# 3-RF.net
KiCad netlist of a schematic drawn in Altium Designer
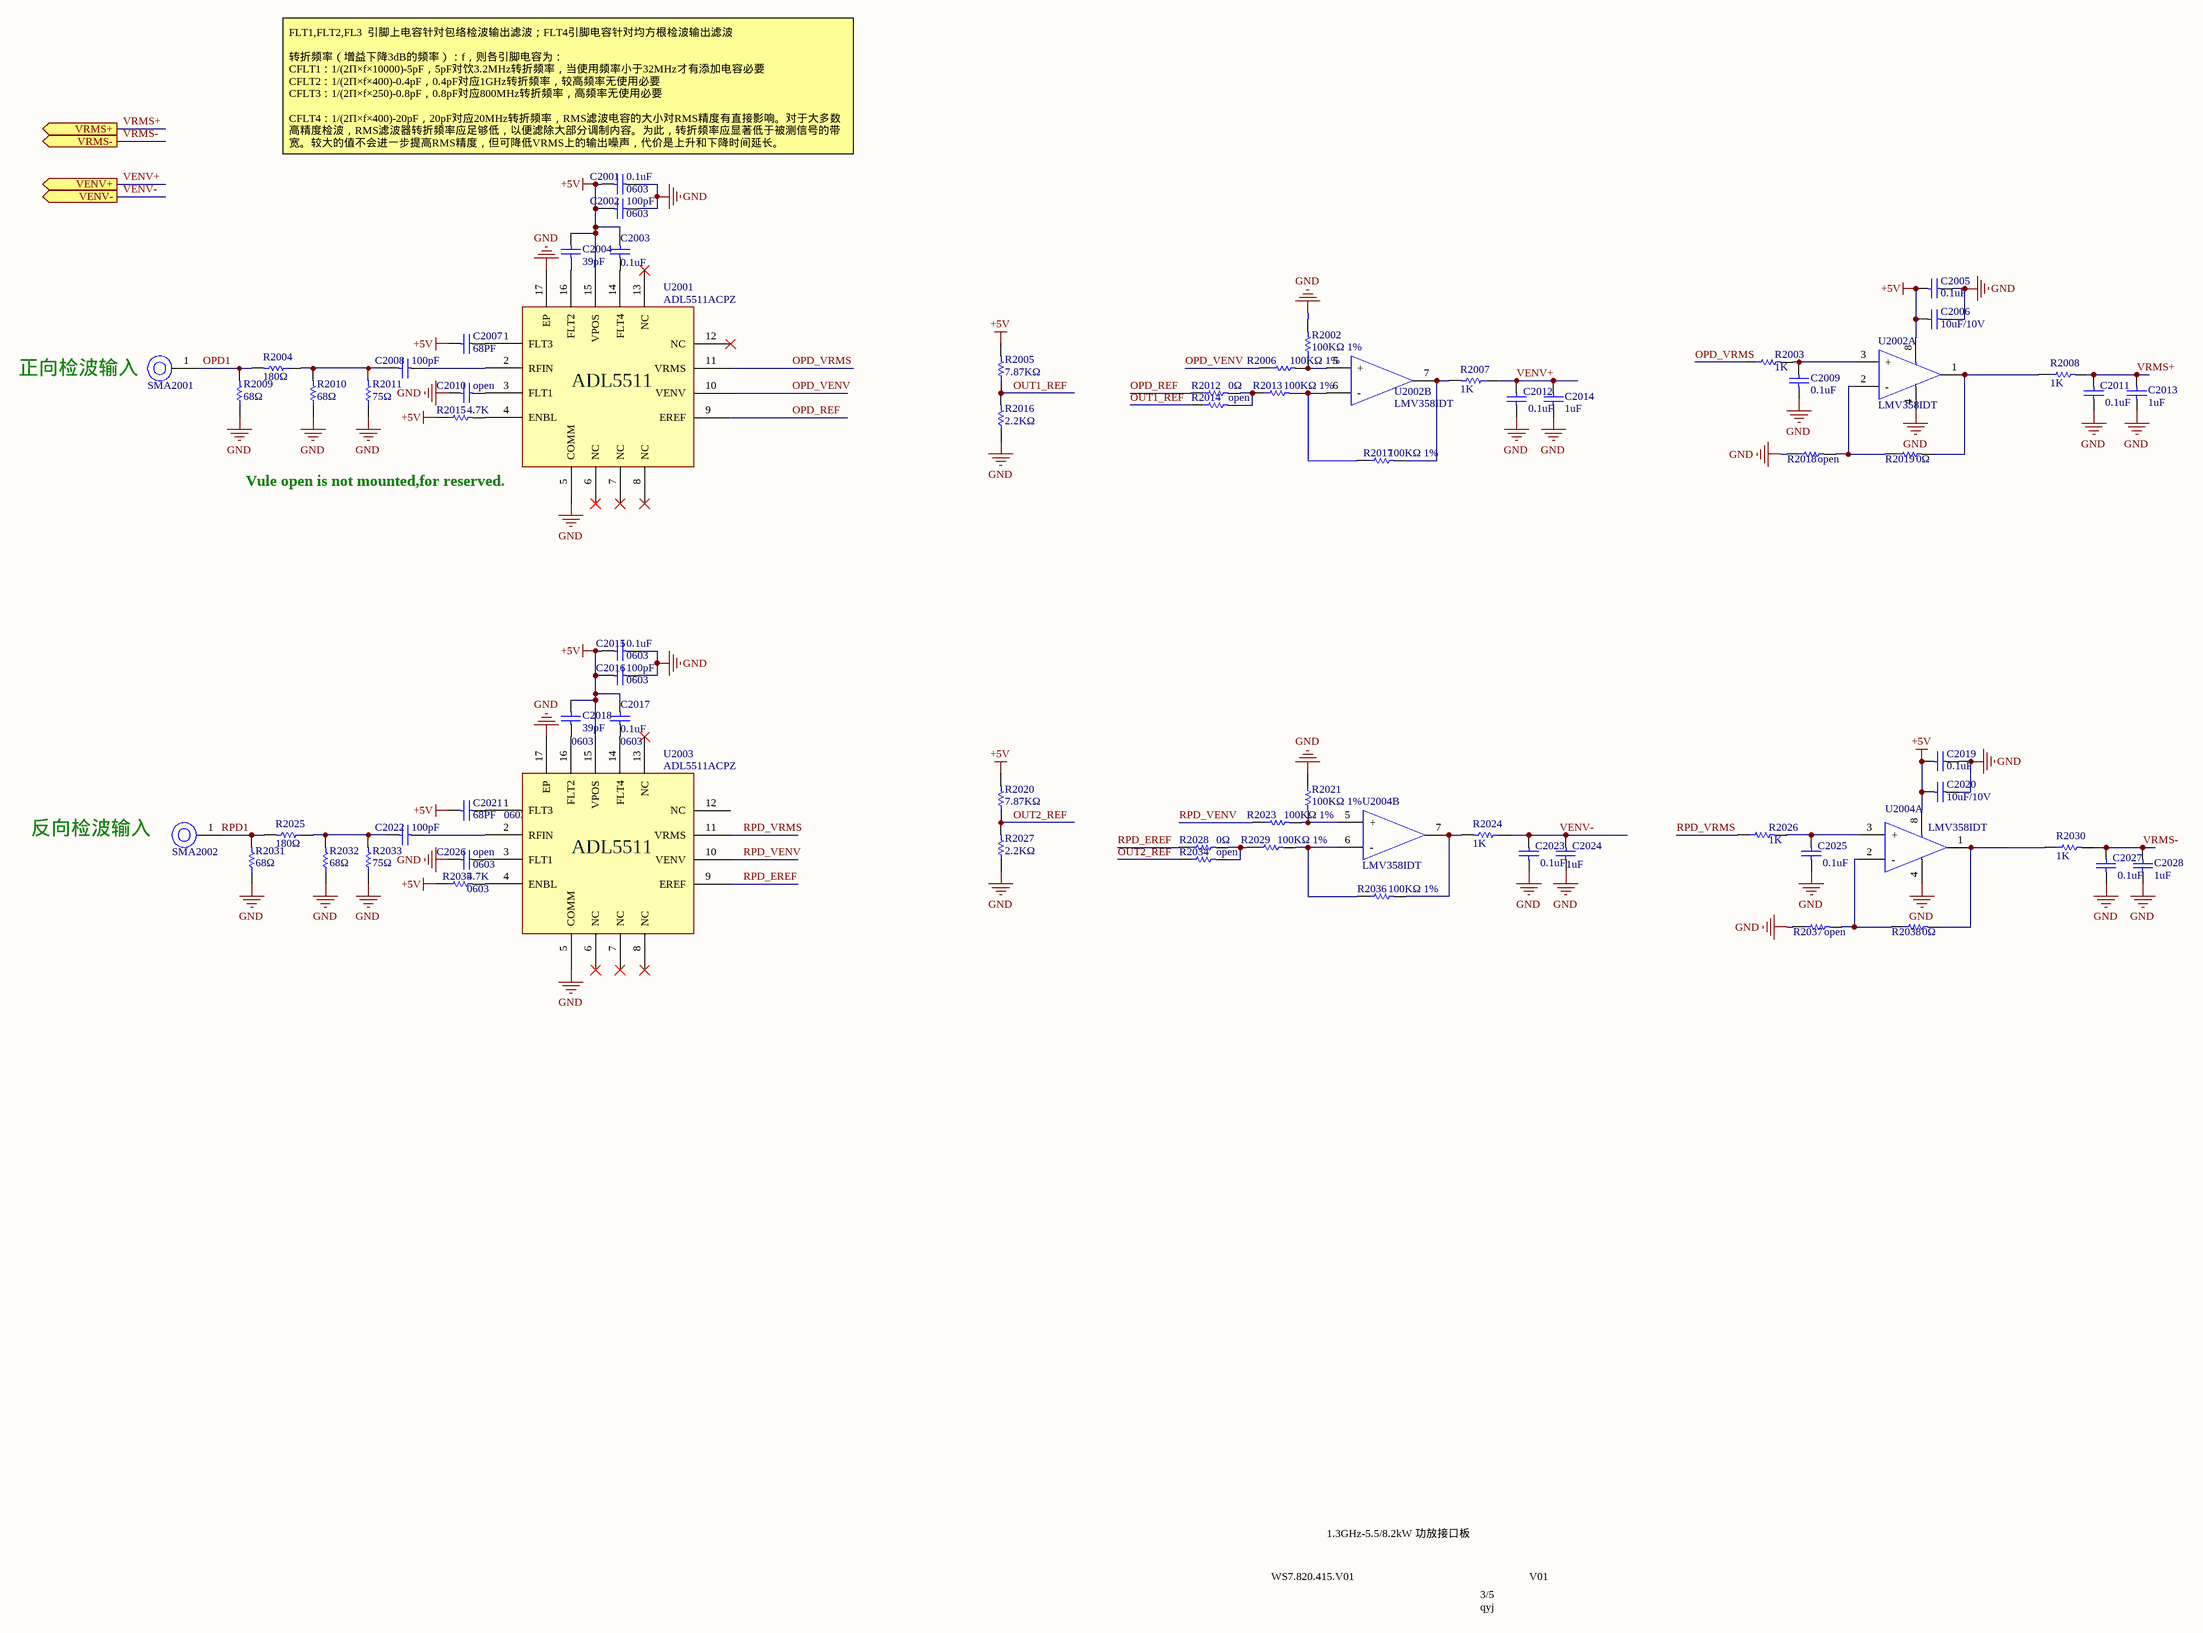
[diagram p0: 3-RF.SchDoc]

(export (version "E")
  (design (tool "Eeschema 10.0.6"))
  (components
    (comp (ref "C2001")
      (value "0.1uF")
      (footprint "C0603")
      (description "贴片电容_GRM188R71H104KA01D_0.1uF±10%,50V,0603")
      (libsource (lib "20贴片电容0603") (part "0.1uF贴片电容"))
    )
    (comp (ref "C2002")
      (value "100pF")
      (footprint "C0603")
      (description "贴片电容_100pF±10%,50V,0603")
      (libsource (lib "20贴片电容0603") (part "1000pF贴片电容"))
    )
    (comp (ref "C2003")
      (value "0.1uF")
      (footprint "C0603")
      (description "贴片电容_GRM188R71H104KA01D_0.1uF±10%,50V,0603")
      (libsource (lib "20贴片电容0603") (part "0.1uF贴片电容"))
    )
    (comp (ref "C2004")
      (value "39pF")
      (footprint "C0603")
      (description "GRM1885C1H390JA01D_39pF±5%,50V,0603")
      (libsource (lib "20贴片电容0603") (part "10pF贴片电容"))
    )
    (comp (ref "C2005")
      (value "0.1uF")
      (footprint "C0603")
      (description "贴片电容_GRM188R71H104KA01D_0.1uF±10%,50V,0603")
      (libsource (lib "20贴片电容0603") (part "0.1uF贴片电容"))
    )
    (comp (ref "C2006")
      (value "10uF/10V")
      (footprint "C0805")
      (description "贴片电容_GRM21BR61A106KE19L_10uF±10%,10V,0805")
      (libsource (lib "21贴片电容0805") (part "10uF贴片电容"))
    )
    (comp (ref "C2007")
      (value "68PF")
      (footprint "C0603")
      (description "贴片电容_GRM1885C1H680JA01D_0603,68PF,50V,±5％,COG")
      (fields (field (name "MPN") "Murata"))
      (libsource (lib "20贴片电容0603") (part "10pF贴片电容"))
    )
    (comp (ref "C2008")
      (value "100pF")
      (footprint "C0805")
      (description "贴片电容_GRM2165C1H101JA01D_100pF±5%,50V,0805")
      (libsource (lib "21贴片电容0805") (part "100pF贴片电容"))
    )
    (comp (ref "C2009")
      (value "0.1uF")
      (footprint "C0603")
      (description "贴片电容_GRM188R71H104KA01D_0.1uF±10%,50V,0603")
      (libsource (lib "20贴片电容0603") (part "0.1uF贴片电容"))
    )
    (comp (ref "C2010")
      (value "open")
      (footprint "C0603")
      (description "贴片电容_GRM188R71H102KA01_1000pF±10%,50V,0603")
      (libsource (lib "20贴片电容0603") (part "1000pF贴片电容"))
    )
    (comp (ref "C2011")
      (value "0.1uF")
      (footprint "C0603")
      (description "贴片电容_GRM188R71H104KA01D_0.1uF±10%,50V,0603")
      (libsource (lib "20贴片电容0603") (part "0.1uF贴片电容"))
    )
    (comp (ref "C2012")
      (value "0.1uF")
      (footprint "C0603")
      (description "贴片电容_GRM188R71H104KA01D_0.1uF±10%,50V,0603")
      (libsource (lib "20贴片电容0603") (part "0.1uF贴片电容"))
    )
    (comp (ref "C2013")
      (value "1uF")
      (footprint "C0603")
      (description "贴片电容_GRM188R60J106ME47D_10uF±20%,6.3V,0603")
      (libsource (lib "20贴片电容0603") (part "10uF贴片电容"))
    )
    (comp (ref "C2014") (value "1uF") (footprint "C0603") (libsource (lib "20贴片电容0603") (part "10uF贴片电容")))
    (comp (ref "C2015")
      (value "0.1uF")
      (footprint "C0603")
      (description "贴片电容_GRM188R71H104KA01D_0.1uF±10%,50V,0603")
      (libsource (lib "20贴片电容0603") (part "0.1uF贴片电容"))
    )
    (comp (ref "C2016")
      (value "100pF")
      (footprint "C0603")
      (description "贴片电容_100pF±10%,50V,0603")
      (libsource (lib "20贴片电容0603") (part "1000pF贴片电容"))
    )
    (comp (ref "C2017")
      (value "0.1uF")
      (footprint "C0603")
      (description "贴片电容_GRM188R71H104KA01D_0.1uF±10%,50V,0603")
      (libsource (lib "20贴片电容0603") (part "0.1uF贴片电容"))
    )
    (comp (ref "C2018")
      (value "39pF")
      (footprint "C0603")
      (description "GRM1885C1H390JA01D_39pF±5%,50V,0603")
      (libsource (lib "20贴片电容0603") (part "10pF贴片电容"))
    )
    (comp (ref "C2019")
      (value "0.1uF")
      (footprint "C0603")
      (description "贴片电容_GRM188R71H104KA01D_0.1uF±10%,50V,0603")
      (libsource (lib "20贴片电容0603") (part "0.1uF贴片电容"))
    )
    (comp (ref "C2020")
      (value "10uF/10V")
      (footprint "C0805")
      (description "贴片电容_GRM21BR61A106KE19L_10uF±10%,10V,0805")
      (libsource (lib "21贴片电容0805") (part "10uF贴片电容"))
    )
    (comp (ref "C2021")
      (value "68PF")
      (footprint "C0603")
      (description "贴片电容_GRM1885C1H680JA01D_0603,68PF,50V,±5％,COG")
      (fields (field (name "MPN") "Murata"))
      (libsource (lib "20贴片电容0603") (part "10pF贴片电容"))
    )
    (comp (ref "C2022")
      (value "100pF")
      (footprint "C0805")
      (description "贴片电容_GRM2165C1H101JA01D_100pF±5%,50V,0805")
      (libsource (lib "21贴片电容0805") (part "100pF贴片电容"))
    )
    (comp (ref "C2023")
      (value "0.1uF")
      (footprint "C0603")
      (description "贴片电容_GRM188R71H104KA01D_0.1uF±10%,50V,0603")
      (libsource (lib "20贴片电容0603") (part "0.1uF贴片电容"))
    )
    (comp (ref "C2024") (value "1uF") (footprint "C0603") (libsource (lib "20贴片电容0603") (part "10uF贴片电容")))
    (comp (ref "C2025")
      (value "0.1uF")
      (footprint "C0603")
      (description "贴片电容_GRM188R71H104KA01D_0.1uF±10%,50V,0603")
      (libsource (lib "20贴片电容0603") (part "0.1uF贴片电容"))
    )
    (comp (ref "C2026")
      (value "open")
      (footprint "C0603")
      (description "贴片电容_GRM188R71H102KA01_1000pF±10%,50V,0603")
      (libsource (lib "20贴片电容0603") (part "1000pF贴片电容"))
    )
    (comp (ref "C2027")
      (value "0.1uF")
      (footprint "C0603")
      (description "贴片电容_GRM188R71H104KA01D_0.1uF±10%,50V,0603")
      (libsource (lib "20贴片电容0603") (part "0.1uF贴片电容"))
    )
    (comp (ref "C2028")
      (value "1uF")
      (footprint "C0603")
      (description "贴片电容_GRM188R60J106ME47D_10uF±20%,6.3V,0603")
      (libsource (lib "20贴片电容0603") (part "10uF贴片电容"))
    )
    (comp (ref "R2002")
      (value "100KΩ 1%")
      (footprint "R0603")
      (libsource (lib "10贴片电阻0603") (part "430Ω贴片电阻"))
    )
    (comp (ref "R2003")
      (value "1K")
      (footprint "R0603")
      (description "贴片电阻_1K±5%,0603")
      (libsource (lib "10贴片电阻0603") (part "1K贴片电阻"))
    )
    (comp (ref "R2004")
      (value "180Ω")
      (footprint "R1206")
      (description "贴片电阻_1206,180Ω,±5％")
      (libsource (lib "12贴片电阻1206") (part "56Ω贴片电阻"))
    )
    (comp (ref "R2005")
      (value "7.87KΩ")
      (footprint "R0603")
      (description "0603,7.87KΩ,±1％")
      (libsource (lib "10贴片电阻0603") (part "0Ω贴片电阻"))
    )
    (comp (ref "R2006")
      (value "100KΩ 1%")
      (footprint "R0603")
      (libsource (lib "10贴片电阻0603") (part "430Ω贴片电阻"))
    )
    (comp (ref "R2007")
      (value "1K")
      (footprint "R0603")
      (description "贴片电阻_1K±5%,0603")
      (libsource (lib "10贴片电阻0603") (part "10K贴片电阻"))
    )
    (comp (ref "R2008")
      (value "1K")
      (footprint "R0603")
      (description "贴片电阻_1K±5%,0603")
      (libsource (lib "10贴片电阻0603") (part "10K贴片电阻"))
    )
    (comp (ref "R2009")
      (value "68Ω")
      (footprint "R1206")
      (description "贴片电阻_68Ω±5%,1206")
      (libsource (lib "12贴片电阻1206") (part "56Ω贴片电阻"))
    )
    (comp (ref "R2010")
      (value "68Ω")
      (footprint "R1206")
      (description "贴片电阻_68Ω±5%,1206")
      (libsource (lib "12贴片电阻1206") (part "56Ω贴片电阻"))
    )
    (comp (ref "R2011")
      (value "75Ω")
      (footprint "R0805")
      (description "贴片电阻_75Ω±5%,0805")
      (libsource (lib "11贴片电阻0805") (part "75Ω贴片电阻"))
    )
    (comp (ref "R2012")
      (value "0Ω")
      (footprint "R0603")
      (description "贴片电阻_0Ω±5%,0603")
      (libsource (lib "10贴片电阻0603") (part "0Ω贴片电阻"))
    )
    (comp (ref "R2013")
      (value "100KΩ 1%")
      (footprint "R0603")
      (libsource (lib "10贴片电阻0603") (part "430Ω贴片电阻"))
    )
    (comp (ref "R2014")
      (value "open")
      (footprint "R0603")
      (description "贴片电阻_0Ω±5%,0603")
      (libsource (lib "10贴片电阻0603") (part "0Ω贴片电阻"))
    )
    (comp (ref "R2015")
      (value "4.7K")
      (footprint "R0603")
      (description "贴片电阻_4.7K±5%,0603")
      (libsource (lib "10贴片电阻0603") (part "4.7K贴片电阻"))
    )
    (comp (ref "R2016")
      (value "2.2KΩ")
      (footprint "R0603")
      (description "0603,2.2KΩ,±1％")
      (libsource (lib "10贴片电阻0603") (part "0Ω贴片电阻"))
    )
    (comp (ref "R2017")
      (value "100KΩ 1%")
      (footprint "R0603")
      (libsource (lib "10贴片电阻0603") (part "430Ω贴片电阻"))
    )
    (comp (ref "R2018") (value "open") (footprint "R0603") (libsource (lib "10贴片电阻0603") (part "0Ω贴片电阻")))
    (comp (ref "R2019")
      (value "0Ω")
      (footprint "R0603")
      (description "贴片电阻_0Ω±5%,0603")
      (libsource (lib "10贴片电阻0603") (part "0Ω贴片电阻"))
    )
    (comp (ref "R2020")
      (value "7.87KΩ")
      (footprint "R0603")
      (description "0603,7.87KΩ,±1％")
      (libsource (lib "10贴片电阻0603") (part "0Ω贴片电阻"))
    )
    (comp (ref "R2021")
      (value "100KΩ 1%")
      (footprint "R0603")
      (libsource (lib "10贴片电阻0603") (part "430Ω贴片电阻"))
    )
    (comp (ref "R2023")
      (value "100KΩ 1%")
      (footprint "R0603")
      (libsource (lib "10贴片电阻0603") (part "430Ω贴片电阻"))
    )
    (comp (ref "R2024")
      (value "1K")
      (footprint "R0603")
      (description "贴片电阻_1K±5%,0603")
      (libsource (lib "10贴片电阻0603") (part "10K贴片电阻"))
    )
    (comp (ref "R2025")
      (value "180Ω")
      (footprint "R1206")
      (description "贴片电阻_1206,180Ω,±5％")
      (libsource (lib "12贴片电阻1206") (part "56Ω贴片电阻"))
    )
    (comp (ref "R2026")
      (value "1K")
      (footprint "R0603")
      (description "贴片电阻_1K±5%,0603")
      (libsource (lib "10贴片电阻0603") (part "1K贴片电阻"))
    )
    (comp (ref "R2027")
      (value "2.2KΩ")
      (footprint "R0603")
      (description "0603,2.2KΩ,±1％")
      (libsource (lib "10贴片电阻0603") (part "0Ω贴片电阻"))
    )
    (comp (ref "R2028")
      (value "0Ω")
      (footprint "R0603")
      (description "贴片电阻_0Ω±5%,0603")
      (libsource (lib "10贴片电阻0603") (part "0Ω贴片电阻"))
    )
    (comp (ref "R2029")
      (value "100KΩ 1%")
      (footprint "R0603")
      (libsource (lib "10贴片电阻0603") (part "430Ω贴片电阻"))
    )
    (comp (ref "R2030")
      (value "1K")
      (footprint "R0603")
      (description "贴片电阻_1K±5%,0603")
      (libsource (lib "10贴片电阻0603") (part "10K贴片电阻"))
    )
    (comp (ref "R2031")
      (value "68Ω")
      (footprint "R1206")
      (description "贴片电阻_68Ω±5%,1206")
      (libsource (lib "12贴片电阻1206") (part "56Ω贴片电阻"))
    )
    (comp (ref "R2032")
      (value "68Ω")
      (footprint "R1206")
      (description "贴片电阻_68Ω±5%,1206")
      (libsource (lib "12贴片电阻1206") (part "56Ω贴片电阻"))
    )
    (comp (ref "R2033")
      (value "75Ω")
      (footprint "R0805")
      (description "贴片电阻_75Ω±5%,0805")
      (libsource (lib "11贴片电阻0805") (part "75Ω贴片电阻"))
    )
    (comp (ref "R2034")
      (value "open")
      (footprint "R0603")
      (description "贴片电阻_0Ω±5%,0603")
      (libsource (lib "10贴片电阻0603") (part "0Ω贴片电阻"))
    )
    (comp (ref "R2035")
      (value "4.7K")
      (footprint "R0603")
      (description "贴片电阻_4.7K±5%,0603")
      (libsource (lib "10贴片电阻0603") (part "4.7K贴片电阻"))
    )
    (comp (ref "R2036")
      (value "100KΩ 1%")
      (footprint "R0603")
      (libsource (lib "10贴片电阻0603") (part "430Ω贴片电阻"))
    )
    (comp (ref "R2037") (value "open") (footprint "R0603") (libsource (lib "10贴片电阻0603") (part "0Ω贴片电阻")))
    (comp (ref "R2038")
      (value "0Ω")
      (footprint "R0603")
      (description "贴片电阻_0Ω±5%,0603")
      (libsource (lib "10贴片电阻0603") (part "0Ω贴片电阻"))
    )
    (comp (ref "SMA2001")
      (value "SMA-50KFD-4")
      (footprint "SMA-50KFD-4")
      (description "射频同轴连接器_SMA-50KFD-4")
      (libsource (lib "90RF连接器") (part "SMA-50KFD-4"))
    )
    (comp (ref "SMA2002")
      (value "SMA-50KFD-4")
      (footprint "SMA-50KFD-4")
      (description "射频同轴连接器_SMA-50KFD-4")
      (libsource (lib "90RF连接器") (part "SMA-50KFD-4"))
    )
    (comp (ref "U2001")
      (value "ADL5511ACPZ")
      (footprint "QFN16_0R50_3X3")
      (description "检波器_ADL5511ACPZ_DC~6GHz,LFCSP16")
      (libsource (lib "74检波器") (part "ADL5511ACPZ"))
    )
    (comp (ref "U2002")
      (value "LMV358IDT")
      (footprint "SOIC8_1R27_3R9x4R9")
      (libsource (lib "77运算放大器") (part "OP284"))
    )
    (comp (ref "U2003")
      (value "ADL5511ACPZ")
      (footprint "QFN16_0R50_3X3")
      (description "检波器_ADL5511ACPZ_DC~6GHz,LFCSP16")
      (libsource (lib "74检波器") (part "ADL5511ACPZ"))
    )
    (comp (ref "U2004")
      (value "LMV358IDT")
      (footprint "SOIC8_1R27_3R9x4R9")
      (description "运算放大器_LM358_SOIC8")
      (libsource (lib "77运算放大器") (part "LM358"))
    )
  )
  (nets
    (net (code "1") (name "+5V") (class "Default")
      (node (ref "C2001") (pin "2") (pinfunction "2_2") (pintype "passive"))
      (node (ref "C2002") (pin "1") (pinfunction "1_1") (pintype "passive"))
      (node (ref "C2003") (pin "2") (pinfunction "2_2") (pintype "passive"))
      (node (ref "C2004") (pin "2") (pinfunction "2_2") (pintype "passive"))
      (node (ref "C2005") (pin "1") (pinfunction "1_1") (pintype "passive"))
      (node (ref "C2006") (pin "1") (pinfunction "1_1") (pintype "passive"))
      (node (ref "C2007") (pin "1") (pinfunction "1_1") (pintype "passive"))
      (node (ref "C2015") (pin "2") (pinfunction "2_2") (pintype "passive"))
      (node (ref "C2016") (pin "1") (pinfunction "1_1") (pintype "passive"))
      (node (ref "C2017") (pin "2") (pinfunction "2_2") (pintype "passive"))
      (node (ref "C2018") (pin "2") (pinfunction "2_2") (pintype "passive"))
      (node (ref "C2019") (pin "1") (pinfunction "1_1") (pintype "passive"))
      (node (ref "C2020") (pin "1") (pinfunction "1_1") (pintype "passive"))
      (node (ref "C2021") (pin "1") (pinfunction "1_1") (pintype "passive"))
      (node (ref "R2005") (pin "2") (pinfunction "2_2") (pintype "passive"))
      (node (ref "R2015") (pin "1") (pinfunction "1_1") (pintype "passive"))
      (node (ref "R2020") (pin "2") (pinfunction "2_2") (pintype "passive"))
      (node (ref "R2035") (pin "1") (pinfunction "1_1") (pintype "passive"))
      (node (ref "U2001") (pin "15") (pinfunction "VPOS_15") (pintype "passive"))
      (node (ref "U2002") (pin "8") (pintype "passive"))
      (node (ref "U2003") (pin "15") (pinfunction "VPOS_15") (pintype "passive"))
      (node (ref "U2004") (pin "8") (pintype "passive"))
    )
    (net (code "2") (name "/OPD1") (class "Default")
      (node (ref "R2004") (pin "2") (pinfunction "2_2") (pintype "passive"))
      (node (ref "R2009") (pin "2") (pinfunction "2_2") (pintype "passive"))
      (node (ref "SMA2001") (pin "1") (pinfunction "Sig_1") (pintype "passive"))
    )
    (net (code "3") (name "/OPD_REF") (class "Default")
      (node (ref "R2012") (pin "1") (pinfunction "1_1") (pintype "passive"))
      (node (ref "U2001") (pin "9") (pinfunction "EREF_9") (pintype "passive"))
    )
    (net (code "4") (name "/OPD_VENV") (class "Default")
      (node (ref "R2006") (pin "1") (pinfunction "1_1") (pintype "passive"))
      (node (ref "U2001") (pin "10") (pinfunction "VENV_10") (pintype "passive"))
    )
    (net (code "5") (name "/OPD_VRMS") (class "Default")
      (node (ref "R2003") (pin "1") (pinfunction "1_1") (pintype "passive"))
      (node (ref "U2001") (pin "11") (pinfunction "VRMS_11") (pintype "passive"))
    )
    (net (code "6") (name "/OUT1_REF") (class "Default")
      (node (ref "R2005") (pin "1") (pinfunction "1_1") (pintype "passive"))
      (node (ref "R2014") (pin "1") (pinfunction "1_1") (pintype "passive"))
      (node (ref "R2016") (pin "2") (pinfunction "2_2") (pintype "passive"))
    )
    (net (code "7") (name "/OUT2_REF") (class "Default")
      (node (ref "R2020") (pin "1") (pinfunction "1_1") (pintype "passive"))
      (node (ref "R2027") (pin "2") (pinfunction "2_2") (pintype "passive"))
      (node (ref "R2034") (pin "1") (pinfunction "1_1") (pintype "passive"))
    )
    (net (code "8") (name "/RPD1") (class "Default")
      (node (ref "R2025") (pin "2") (pinfunction "2_2") (pintype "passive"))
      (node (ref "R2031") (pin "2") (pinfunction "2_2") (pintype "passive"))
      (node (ref "SMA2002") (pin "1") (pinfunction "Sig_1") (pintype "passive"))
    )
    (net (code "9") (name "/RPD_EREF") (class "Default")
      (node (ref "R2028") (pin "1") (pinfunction "1_1") (pintype "passive"))
      (node (ref "U2003") (pin "9") (pinfunction "EREF_9") (pintype "passive"))
    )
    (net (code "10") (name "/RPD_VENV") (class "Default")
      (node (ref "R2023") (pin "1") (pinfunction "1_1") (pintype "passive"))
      (node (ref "U2003") (pin "10") (pinfunction "VENV_10") (pintype "passive"))
    )
    (net (code "11") (name "/RPD_VRMS") (class "Default")
      (node (ref "R2026") (pin "1") (pinfunction "1_1") (pintype "passive"))
      (node (ref "U2003") (pin "11") (pinfunction "VRMS_11") (pintype "passive"))
    )
    (net (code "12") (name "/VENV+") (class "Default")
      (node (ref "C2012") (pin "2") (pinfunction "2_2") (pintype "passive"))
      (node (ref "C2014") (pin "2") (pinfunction "2_2") (pintype "passive"))
      (node (ref "R2007") (pin "1") (pinfunction "1_1") (pintype "passive"))
    )
    (net (code "13") (name "/VENV-") (class "Default")
      (node (ref "C2023") (pin "2") (pinfunction "2_2") (pintype "passive"))
      (node (ref "C2024") (pin "2") (pinfunction "2_2") (pintype "passive"))
      (node (ref "R2024") (pin "1") (pinfunction "1_1") (pintype "passive"))
    )
    (net (code "14") (name "/VRMS+") (class "Default")
      (node (ref "C2011") (pin "2") (pinfunction "2_2") (pintype "passive"))
      (node (ref "C2013") (pin "2") (pinfunction "2_2") (pintype "passive"))
      (node (ref "R2008") (pin "2") (pinfunction "2_2") (pintype "passive"))
    )
    (net (code "15") (name "/VRMS-") (class "Default")
      (node (ref "C2027") (pin "2") (pinfunction "2_2") (pintype "passive"))
      (node (ref "C2028") (pin "2") (pinfunction "2_2") (pintype "passive"))
      (node (ref "R2030") (pin "2") (pinfunction "2_2") (pintype "passive"))
    )
    (net (code "16") (name "GND") (class "Default")
      (node (ref "C2001") (pin "1") (pinfunction "1_1") (pintype "passive"))
      (node (ref "C2002") (pin "2") (pinfunction "2_2") (pintype "passive"))
      (node (ref "C2005") (pin "2") (pinfunction "2_2") (pintype "passive"))
      (node (ref "C2006") (pin "2") (pinfunction "2_2") (pintype "passive"))
      (node (ref "C2009") (pin "1") (pinfunction "1_1") (pintype "passive"))
      (node (ref "C2010") (pin "1") (pinfunction "1_1") (pintype "passive"))
      (node (ref "C2011") (pin "1") (pinfunction "1_1") (pintype "passive"))
      (node (ref "C2012") (pin "1") (pinfunction "1_1") (pintype "passive"))
      (node (ref "C2013") (pin "1") (pinfunction "1_1") (pintype "passive"))
      (node (ref "C2014") (pin "1") (pinfunction "1_1") (pintype "passive"))
      (node (ref "C2015") (pin "1") (pinfunction "1_1") (pintype "passive"))
      (node (ref "C2016") (pin "2") (pinfunction "2_2") (pintype "passive"))
      (node (ref "C2019") (pin "2") (pinfunction "2_2") (pintype "passive"))
      (node (ref "C2020") (pin "2") (pinfunction "2_2") (pintype "passive"))
      (node (ref "C2023") (pin "1") (pinfunction "1_1") (pintype "passive"))
      (node (ref "C2024") (pin "1") (pinfunction "1_1") (pintype "passive"))
      (node (ref "C2025") (pin "1") (pinfunction "1_1") (pintype "passive"))
      (node (ref "C2026") (pin "1") (pinfunction "1_1") (pintype "passive"))
      (node (ref "C2027") (pin "1") (pinfunction "1_1") (pintype "passive"))
      (node (ref "C2028") (pin "1") (pinfunction "1_1") (pintype "passive"))
      (node (ref "R2002") (pin "2") (pinfunction "2_2") (pintype "passive"))
      (node (ref "R2009") (pin "1") (pinfunction "1_1") (pintype "passive"))
      (node (ref "R2010") (pin "1") (pinfunction "1_1") (pintype "passive"))
      (node (ref "R2011") (pin "1") (pinfunction "1_1") (pintype "passive"))
      (node (ref "R2016") (pin "1") (pinfunction "1_1") (pintype "passive"))
      (node (ref "R2018") (pin "1") (pinfunction "1_1") (pintype "passive"))
      (node (ref "R2021") (pin "1") (pinfunction "1_1") (pintype "passive"))
      (node (ref "R2027") (pin "1") (pinfunction "1_1") (pintype "passive"))
      (node (ref "R2031") (pin "1") (pinfunction "1_1") (pintype "passive"))
      (node (ref "R2032") (pin "1") (pinfunction "1_1") (pintype "passive"))
      (node (ref "R2033") (pin "1") (pinfunction "1_1") (pintype "passive"))
      (node (ref "R2037") (pin "1") (pinfunction "1_1") (pintype "passive"))
      (node (ref "U2001") (pin "17") (pinfunction "EP_17") (pintype "power_in"))
      (node (ref "U2001") (pin "5") (pinfunction "COMM_5") (pintype "passive"))
      (node (ref "U2002") (pin "4") (pintype "passive"))
      (node (ref "U2003") (pin "17") (pinfunction "EP_17") (pintype "power_in"))
      (node (ref "U2003") (pin "5") (pinfunction "COMM_5") (pintype "passive"))
      (node (ref "U2004") (pin "4") (pintype "passive"))
    )
    (net (code "17") (name "Net-(C2008-Pad1)") (class "Default")
      (node (ref "C2008") (pin "1") (pinfunction "1_1") (pintype "passive"))
      (node (ref "R2004") (pin "1") (pinfunction "1_1") (pintype "passive"))
      (node (ref "R2010") (pin "2") (pinfunction "2_2") (pintype "passive"))
      (node (ref "R2011") (pin "2") (pinfunction "2_2") (pintype "passive"))
    )
    (net (code "18") (name "Net-(C2022-Pad1)") (class "Default")
      (node (ref "C2022") (pin "1") (pinfunction "1_1") (pintype "passive"))
      (node (ref "R2025") (pin "1") (pinfunction "1_1") (pintype "passive"))
      (node (ref "R2032") (pin "2") (pinfunction "2_2") (pintype "passive"))
      (node (ref "R2033") (pin "2") (pinfunction "2_2") (pintype "passive"))
    )
    (net (code "19") (name "Net-(R2007-Pad2)") (class "Default")
      (node (ref "R2007") (pin "2") (pinfunction "2_2") (pintype "passive"))
      (node (ref "R2017") (pin "2") (pinfunction "2_2") (pintype "passive"))
      (node (ref "U2002") (pin "7") (pintype "passive"))
    )
    (net (code "20") (name "Net-(R2008-Pad1)") (class "Default")
      (node (ref "R2008") (pin "1") (pinfunction "1_1") (pintype "passive"))
      (node (ref "R2019") (pin "2") (pinfunction "2_2") (pintype "passive"))
      (node (ref "U2002") (pin "1") (pintype "passive"))
    )
    (net (code "21") (name "Net-(R2012-Pad2)") (class "Default")
      (node (ref "R2012") (pin "2") (pinfunction "2_2") (pintype "passive"))
      (node (ref "R2013") (pin "1") (pinfunction "1_1") (pintype "passive"))
      (node (ref "R2014") (pin "2") (pinfunction "2_2") (pintype "passive"))
    )
    (net (code "22") (name "Net-(R2024-Pad2)") (class "Default")
      (node (ref "R2024") (pin "2") (pinfunction "2_2") (pintype "passive"))
      (node (ref "R2036") (pin "2") (pinfunction "2_2") (pintype "passive"))
      (node (ref "U2004") (pin "7") (pintype "passive"))
    )
    (net (code "23") (name "Net-(R2028-Pad2)") (class "Default")
      (node (ref "R2028") (pin "2") (pinfunction "2_2") (pintype "passive"))
      (node (ref "R2029") (pin "1") (pinfunction "1_1") (pintype "passive"))
      (node (ref "R2034") (pin "2") (pinfunction "2_2") (pintype "passive"))
    )
    (net (code "24") (name "Net-(R2030-Pad1)") (class "Default")
      (node (ref "R2030") (pin "1") (pinfunction "1_1") (pintype "passive"))
      (node (ref "R2038") (pin "2") (pinfunction "2_2") (pintype "passive"))
      (node (ref "U2004") (pin "1") (pintype "passive"))
    )
    (net (code "25") (name "Net-(U2001-ENBL)") (class "Default")
      (node (ref "R2015") (pin "2") (pinfunction "2_2") (pintype "passive"))
      (node (ref "U2001") (pin "4") (pinfunction "ENBL_4") (pintype "passive"))
    )
    (net (code "26") (name "Net-(U2001-FLT1)") (class "Default")
      (node (ref "C2010") (pin "2") (pinfunction "2_2") (pintype "passive"))
      (node (ref "U2001") (pin "3") (pinfunction "FLT1_3") (pintype "passive"))
    )
    (net (code "27") (name "Net-(U2001-FLT2)") (class "Default")
      (node (ref "C2004") (pin "1") (pinfunction "1_1") (pintype "passive"))
      (node (ref "U2001") (pin "16") (pinfunction "FLT2_16") (pintype "passive"))
    )
    (net (code "28") (name "Net-(U2001-FLT3)") (class "Default")
      (node (ref "C2007") (pin "2") (pinfunction "2_2") (pintype "passive"))
      (node (ref "U2001") (pin "1") (pinfunction "FLT3_1") (pintype "passive"))
    )
    (net (code "29") (name "Net-(U2001-FLT4)") (class "Default")
      (node (ref "C2003") (pin "1") (pinfunction "1_1") (pintype "passive"))
      (node (ref "U2001") (pin "14") (pinfunction "FLT4_14") (pintype "passive"))
    )
    (net (code "30") (name "Net-(U2001-RFIN)") (class "Default")
      (node (ref "C2008") (pin "2") (pinfunction "2_2") (pintype "passive"))
      (node (ref "U2001") (pin "2") (pinfunction "RFIN_2") (pintype "passive"))
    )
    (net (code "31") (name "Net-(U2002A-+)") (class "Default")
      (node (ref "C2009") (pin "2") (pinfunction "2_2") (pintype "passive"))
      (node (ref "R2003") (pin "2") (pinfunction "2_2") (pintype "passive"))
      (node (ref "U2002") (pin "3") (pinfunction "+_3") (pintype "passive"))
    )
    (net (code "32") (name "Net-(U2002A--)") (class "Default")
      (node (ref "R2018") (pin "2") (pinfunction "2_2") (pintype "passive"))
      (node (ref "R2019") (pin "1") (pinfunction "1_1") (pintype "passive"))
      (node (ref "U2002") (pin "2") (pinfunction "-_2") (pintype "passive"))
    )
    (net (code "33") (name "Net-(U2002B-+)") (class "Default")
      (node (ref "R2002") (pin "1") (pinfunction "1_1") (pintype "passive"))
      (node (ref "R2006") (pin "2") (pinfunction "2_2") (pintype "passive"))
      (node (ref "U2002") (pin "5") (pinfunction "+_5") (pintype "passive"))
    )
    (net (code "34") (name "Net-(U2002B--)") (class "Default")
      (node (ref "R2013") (pin "2") (pinfunction "2_2") (pintype "passive"))
      (node (ref "R2017") (pin "1") (pinfunction "1_1") (pintype "passive"))
      (node (ref "U2002") (pin "6") (pinfunction "-_6") (pintype "passive"))
    )
    (net (code "35") (name "Net-(U2003-ENBL)") (class "Default")
      (node (ref "R2035") (pin "2") (pinfunction "2_2") (pintype "passive"))
      (node (ref "U2003") (pin "4") (pinfunction "ENBL_4") (pintype "passive"))
    )
    (net (code "36") (name "Net-(U2003-FLT1)") (class "Default")
      (node (ref "C2026") (pin "2") (pinfunction "2_2") (pintype "passive"))
      (node (ref "U2003") (pin "3") (pinfunction "FLT1_3") (pintype "passive"))
    )
    (net (code "37") (name "Net-(U2003-FLT2)") (class "Default")
      (node (ref "C2018") (pin "1") (pinfunction "1_1") (pintype "passive"))
      (node (ref "U2003") (pin "16") (pinfunction "FLT2_16") (pintype "passive"))
    )
    (net (code "38") (name "Net-(U2003-FLT3)") (class "Default")
      (node (ref "C2021") (pin "2") (pinfunction "2_2") (pintype "passive"))
      (node (ref "U2003") (pin "1") (pinfunction "FLT3_1") (pintype "passive"))
    )
    (net (code "39") (name "Net-(U2003-FLT4)") (class "Default")
      (node (ref "C2017") (pin "1") (pinfunction "1_1") (pintype "passive"))
      (node (ref "U2003") (pin "14") (pinfunction "FLT4_14") (pintype "passive"))
    )
    (net (code "40") (name "Net-(U2003-RFIN)") (class "Default")
      (node (ref "C2022") (pin "2") (pinfunction "2_2") (pintype "passive"))
      (node (ref "U2003") (pin "2") (pinfunction "RFIN_2") (pintype "passive"))
    )
    (net (code "41") (name "Net-(U2004A-+)") (class "Default")
      (node (ref "C2025") (pin "2") (pinfunction "2_2") (pintype "passive"))
      (node (ref "R2026") (pin "2") (pinfunction "2_2") (pintype "passive"))
      (node (ref "U2004") (pin "3") (pinfunction "+_3") (pintype "passive"))
    )
    (net (code "42") (name "Net-(U2004A--)") (class "Default")
      (node (ref "R2037") (pin "2") (pinfunction "2_2") (pintype "passive"))
      (node (ref "R2038") (pin "1") (pinfunction "1_1") (pintype "passive"))
      (node (ref "U2004") (pin "2") (pinfunction "-_2") (pintype "passive"))
    )
    (net (code "43") (name "Net-(U2004B-+)") (class "Default")
      (node (ref "R2021") (pin "2") (pinfunction "2_2") (pintype "passive"))
      (node (ref "R2023") (pin "2") (pinfunction "2_2") (pintype "passive"))
      (node (ref "U2004") (pin "5") (pinfunction "+_5") (pintype "passive"))
    )
    (net (code "44") (name "Net-(U2004B--)") (class "Default")
      (node (ref "R2029") (pin "2") (pinfunction "2_2") (pintype "passive"))
      (node (ref "R2036") (pin "1") (pinfunction "1_1") (pintype "passive"))
      (node (ref "U2004") (pin "6") (pinfunction "-_6") (pintype "passive"))
    )
    (net (code "45") (name "unconnected-(U2001-NC-Pad6)") (class "Default")
      (node (ref "U2001") (pin "6") (pinfunction "NC_6") (pintype "passive+no_connect"))
    )
    (net (code "46") (name "unconnected-(U2001-NC-Pad7)") (class "Default")
      (node (ref "U2001") (pin "7") (pinfunction "NC_7") (pintype "passive+no_connect"))
    )
    (net (code "47") (name "unconnected-(U2001-NC-Pad8)") (class "Default")
      (node (ref "U2001") (pin "8") (pinfunction "NC_8") (pintype "passive+no_connect"))
    )
    (net (code "48") (name "unconnected-(U2001-NC-Pad12)") (class "Default")
      (node (ref "U2001") (pin "12") (pinfunction "NC_12") (pintype "passive+no_connect"))
    )
    (net (code "49") (name "unconnected-(U2001-NC-Pad13)") (class "Default")
      (node (ref "U2001") (pin "13") (pinfunction "NC_13") (pintype "passive+no_connect"))
    )
    (net (code "50") (name "unconnected-(U2003-NC-Pad6)") (class "Default")
      (node (ref "U2003") (pin "6") (pinfunction "NC_6") (pintype "passive+no_connect"))
    )
    (net (code "51") (name "unconnected-(U2003-NC-Pad7)") (class "Default")
      (node (ref "U2003") (pin "7") (pinfunction "NC_7") (pintype "passive+no_connect"))
    )
    (net (code "52") (name "unconnected-(U2003-NC-Pad8)") (class "Default")
      (node (ref "U2003") (pin "8") (pinfunction "NC_8") (pintype "passive+no_connect"))
    )
    (net (code "53") (name "unconnected-(U2003-NC-Pad12)") (class "Default")
      (node (ref "U2003") (pin "12") (pinfunction "NC_12") (pintype "passive"))
    )
    (net (code "54") (name "unconnected-(U2003-NC-Pad13)") (class "Default")
      (node (ref "U2003") (pin "13") (pinfunction "NC_13") (pintype "passive+no_connect"))
    )
  )
)
